# RNS_Board.net
KiCad netlist of a schematic drawn in EAGLE
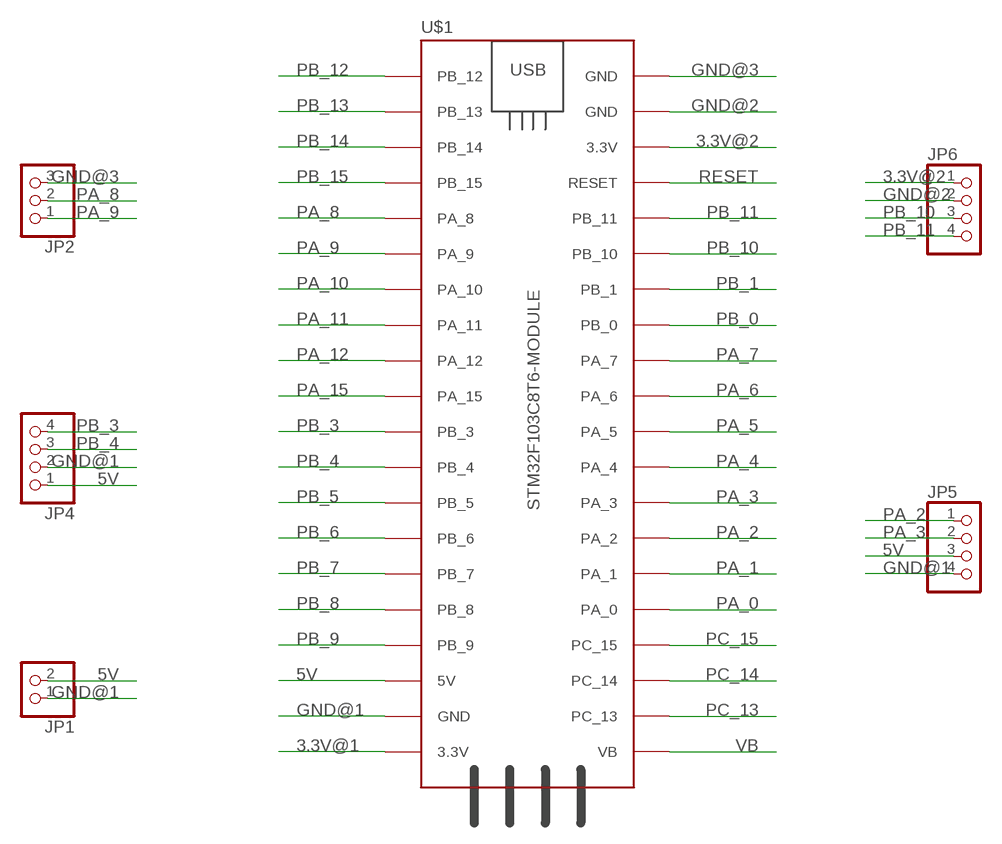
[diagram p0: schematic, sheet 1]

(export (version "E")
  (design (tool "Eeschema 10.0.6"))
  (components
    (comp (ref "JP1")
      (value "PINHD-1X2")
      (footprint "eagle-import:1X02")
      (libsource (lib "eagle-import") (part "PINHD-1X2"))
    )
    (comp (ref "JP2")
      (value "PINHD-1X3")
      (footprint "eagle-import:1X03")
      (libsource (lib "eagle-import") (part "PINHD-1X3"))
    )
    (comp (ref "JP4")
      (value "PINHD-1X4")
      (footprint "eagle-import:1X04")
      (libsource (lib "eagle-import") (part "PINHD-1X4"))
    )
    (comp (ref "JP5")
      (value "PINHD-1X4")
      (footprint "eagle-import:1X04")
      (libsource (lib "eagle-import") (part "PINHD-1X4"))
    )
    (comp (ref "JP6")
      (value "PINHD-1X4")
      (footprint "eagle-import:1X04")
      (libsource (lib "eagle-import") (part "PINHD-1X4"))
    )
    (comp (ref "U$1")
      (value "STM32F103C8T6-MODULE")
      (footprint "eagle-import:STM32F103C8T6-MODULE")
      (libsource (lib "eagle-import") (part "STM32F103C8T6-MODULE"))
    )
  )
  (nets
    (net (code "1") (name "/3.3V@1") (class "Default")
      (node (ref "U$1") (pin "3.3V_1") (pinfunction "3.3V_3.3V_1") (pintype "bidirectional"))
    )
    (net (code "2") (name "/3.3V@2") (class "Default")
      (node (ref "JP6") (pin "1") (pinfunction "1_1") (pintype "passive"))
      (node (ref "U$1") (pin "3.3V_2") (pinfunction "3.3V_3.3V_2") (pintype "bidirectional"))
    )
    (net (code "3") (name "/5V") (class "Default")
      (node (ref "JP1") (pin "2") (pinfunction "2_2") (pintype "passive"))
      (node (ref "JP4") (pin "1") (pinfunction "1_1") (pintype "passive"))
      (node (ref "JP5") (pin "3") (pinfunction "3_3") (pintype "passive"))
      (node (ref "U$1") (pin "5V") (pinfunction "5V_5V") (pintype "bidirectional"))
    )
    (net (code "4") (name "/GND@1") (class "Default")
      (node (ref "JP1") (pin "1") (pinfunction "1_1") (pintype "passive"))
      (node (ref "JP4") (pin "2") (pinfunction "2_2") (pintype "passive"))
      (node (ref "JP5") (pin "4") (pinfunction "4_4") (pintype "passive"))
      (node (ref "U$1") (pin "GND_1") (pinfunction "GND_GND_1") (pintype "bidirectional"))
    )
    (net (code "5") (name "/GND@2") (class "Default")
      (node (ref "JP6") (pin "2") (pinfunction "2_2") (pintype "passive"))
      (node (ref "U$1") (pin "GND_2") (pinfunction "GND_GND_2") (pintype "bidirectional"))
    )
    (net (code "6") (name "/GND@3") (class "Default")
      (node (ref "JP2") (pin "3") (pinfunction "3_3") (pintype "passive"))
      (node (ref "U$1") (pin "GND_3") (pinfunction "GND_GND_3") (pintype "power_in"))
    )
    (net (code "7") (name "/PA_0") (class "Default")
      (node (ref "U$1") (pin "PA_0") (pinfunction "PA_0_PA_0") (pintype "bidirectional"))
    )
    (net (code "8") (name "/PA_1") (class "Default")
      (node (ref "U$1") (pin "PA_1") (pinfunction "PA_1_PA_1") (pintype "bidirectional"))
    )
    (net (code "9") (name "/PA_2") (class "Default")
      (node (ref "JP5") (pin "1") (pinfunction "1_1") (pintype "passive"))
      (node (ref "U$1") (pin "PA_2") (pinfunction "PA_2_PA_2") (pintype "bidirectional"))
    )
    (net (code "10") (name "/PA_3") (class "Default")
      (node (ref "JP5") (pin "2") (pinfunction "2_2") (pintype "passive"))
      (node (ref "U$1") (pin "PA_3") (pinfunction "PA_3_PA_3") (pintype "bidirectional"))
    )
    (net (code "11") (name "/PA_4") (class "Default")
      (node (ref "U$1") (pin "PA_4") (pinfunction "PA_4_PA_4") (pintype "bidirectional"))
    )
    (net (code "12") (name "/PA_5") (class "Default")
      (node (ref "U$1") (pin "PA_5") (pinfunction "PA_5_PA_5") (pintype "bidirectional"))
    )
    (net (code "13") (name "/PA_6") (class "Default")
      (node (ref "U$1") (pin "PA_6") (pinfunction "PA_6_PA_6") (pintype "bidirectional"))
    )
    (net (code "14") (name "/PA_7") (class "Default")
      (node (ref "U$1") (pin "PA_7") (pinfunction "PA_7_PA_7") (pintype "bidirectional"))
    )
    (net (code "15") (name "/PA_8") (class "Default")
      (node (ref "JP2") (pin "2") (pinfunction "2_2") (pintype "passive"))
      (node (ref "U$1") (pin "PA_8") (pinfunction "PA_8_PA_8") (pintype "bidirectional"))
    )
    (net (code "16") (name "/PA_9") (class "Default")
      (node (ref "JP2") (pin "1") (pinfunction "1_1") (pintype "passive"))
      (node (ref "U$1") (pin "PA_9") (pinfunction "PA_9_PA_9") (pintype "bidirectional"))
    )
    (net (code "17") (name "/PA_10") (class "Default")
      (node (ref "U$1") (pin "PA_10") (pinfunction "PA_10_PA_10") (pintype "bidirectional"))
    )
    (net (code "18") (name "/PA_11") (class "Default")
      (node (ref "U$1") (pin "PA_11") (pinfunction "PA_11_PA_11") (pintype "bidirectional"))
    )
    (net (code "19") (name "/PA_12") (class "Default")
      (node (ref "U$1") (pin "PA_12") (pinfunction "PA_12_PA_12") (pintype "bidirectional"))
    )
    (net (code "20") (name "/PA_15") (class "Default")
      (node (ref "U$1") (pin "PA_15") (pinfunction "PA_15_PA_15") (pintype "bidirectional"))
    )
    (net (code "21") (name "/PB_0") (class "Default")
      (node (ref "U$1") (pin "PB_0") (pinfunction "PB_0_PB_0") (pintype "bidirectional"))
    )
    (net (code "22") (name "/PB_1") (class "Default")
      (node (ref "U$1") (pin "PB_1") (pinfunction "PB_1_PB_1") (pintype "bidirectional"))
    )
    (net (code "23") (name "/PB_3") (class "Default")
      (node (ref "JP4") (pin "4") (pinfunction "4_4") (pintype "passive"))
      (node (ref "U$1") (pin "PB_3") (pinfunction "PB_3_PB_3") (pintype "bidirectional"))
    )
    (net (code "24") (name "/PB_4") (class "Default")
      (node (ref "JP4") (pin "3") (pinfunction "3_3") (pintype "passive"))
      (node (ref "U$1") (pin "PB_4") (pinfunction "PB_4_PB_4") (pintype "bidirectional"))
    )
    (net (code "25") (name "/PB_5") (class "Default")
      (node (ref "U$1") (pin "PB_5") (pinfunction "PB_5_PB_5") (pintype "bidirectional"))
    )
    (net (code "26") (name "/PB_6") (class "Default")
      (node (ref "U$1") (pin "PB_6") (pinfunction "PB_6_PB_6") (pintype "bidirectional"))
    )
    (net (code "27") (name "/PB_7") (class "Default")
      (node (ref "U$1") (pin "PB_7") (pinfunction "PB_7_PB_7") (pintype "bidirectional"))
    )
    (net (code "28") (name "/PB_8") (class "Default")
      (node (ref "U$1") (pin "PB_8") (pinfunction "PB_8_PB_8") (pintype "bidirectional"))
    )
    (net (code "29") (name "/PB_9") (class "Default")
      (node (ref "U$1") (pin "PB_9") (pinfunction "PB_9_PB_9") (pintype "bidirectional"))
    )
    (net (code "30") (name "/PB_10") (class "Default")
      (node (ref "JP6") (pin "3") (pinfunction "3_3") (pintype "passive"))
      (node (ref "U$1") (pin "PB_10") (pinfunction "PB_10_PB_10") (pintype "bidirectional"))
    )
    (net (code "31") (name "/PB_11") (class "Default")
      (node (ref "JP6") (pin "4") (pinfunction "4_4") (pintype "passive"))
      (node (ref "U$1") (pin "PB_11") (pinfunction "PB_11_PB_11") (pintype "bidirectional"))
    )
    (net (code "32") (name "/PB_12") (class "Default")
      (node (ref "U$1") (pin "PB_12") (pinfunction "PB_12_PB_12") (pintype "bidirectional"))
    )
    (net (code "33") (name "/PB_13") (class "Default")
      (node (ref "U$1") (pin "PB_13") (pinfunction "PB_13_PB_13") (pintype "bidirectional"))
    )
    (net (code "34") (name "/PB_14") (class "Default")
      (node (ref "U$1") (pin "PB_14") (pinfunction "PB_14_PB_14") (pintype "bidirectional"))
    )
    (net (code "35") (name "/PB_15") (class "Default")
      (node (ref "U$1") (pin "PB_15") (pinfunction "PB_15_PB_15") (pintype "bidirectional"))
    )
    (net (code "36") (name "/PC_13") (class "Default")
      (node (ref "U$1") (pin "PC_13") (pinfunction "PC_13_PC_13") (pintype "bidirectional"))
    )
    (net (code "37") (name "/PC_14") (class "Default")
      (node (ref "U$1") (pin "PC_14") (pinfunction "PC_14_PC_14") (pintype "bidirectional"))
    )
    (net (code "38") (name "/PC_15") (class "Default")
      (node (ref "U$1") (pin "PC_15") (pinfunction "PC_15_PC_15") (pintype "bidirectional"))
    )
    (net (code "39") (name "/RESET") (class "Default")
      (node (ref "U$1") (pin "RESET") (pinfunction "RESET_RESET") (pintype "bidirectional"))
    )
    (net (code "40") (name "/VB") (class "Default")
      (node (ref "U$1") (pin "VB") (pinfunction "VB_VB") (pintype "bidirectional"))
    )
  )
)
